# AC.net
KiCad netlist of a schematic drawn in Altium Designer
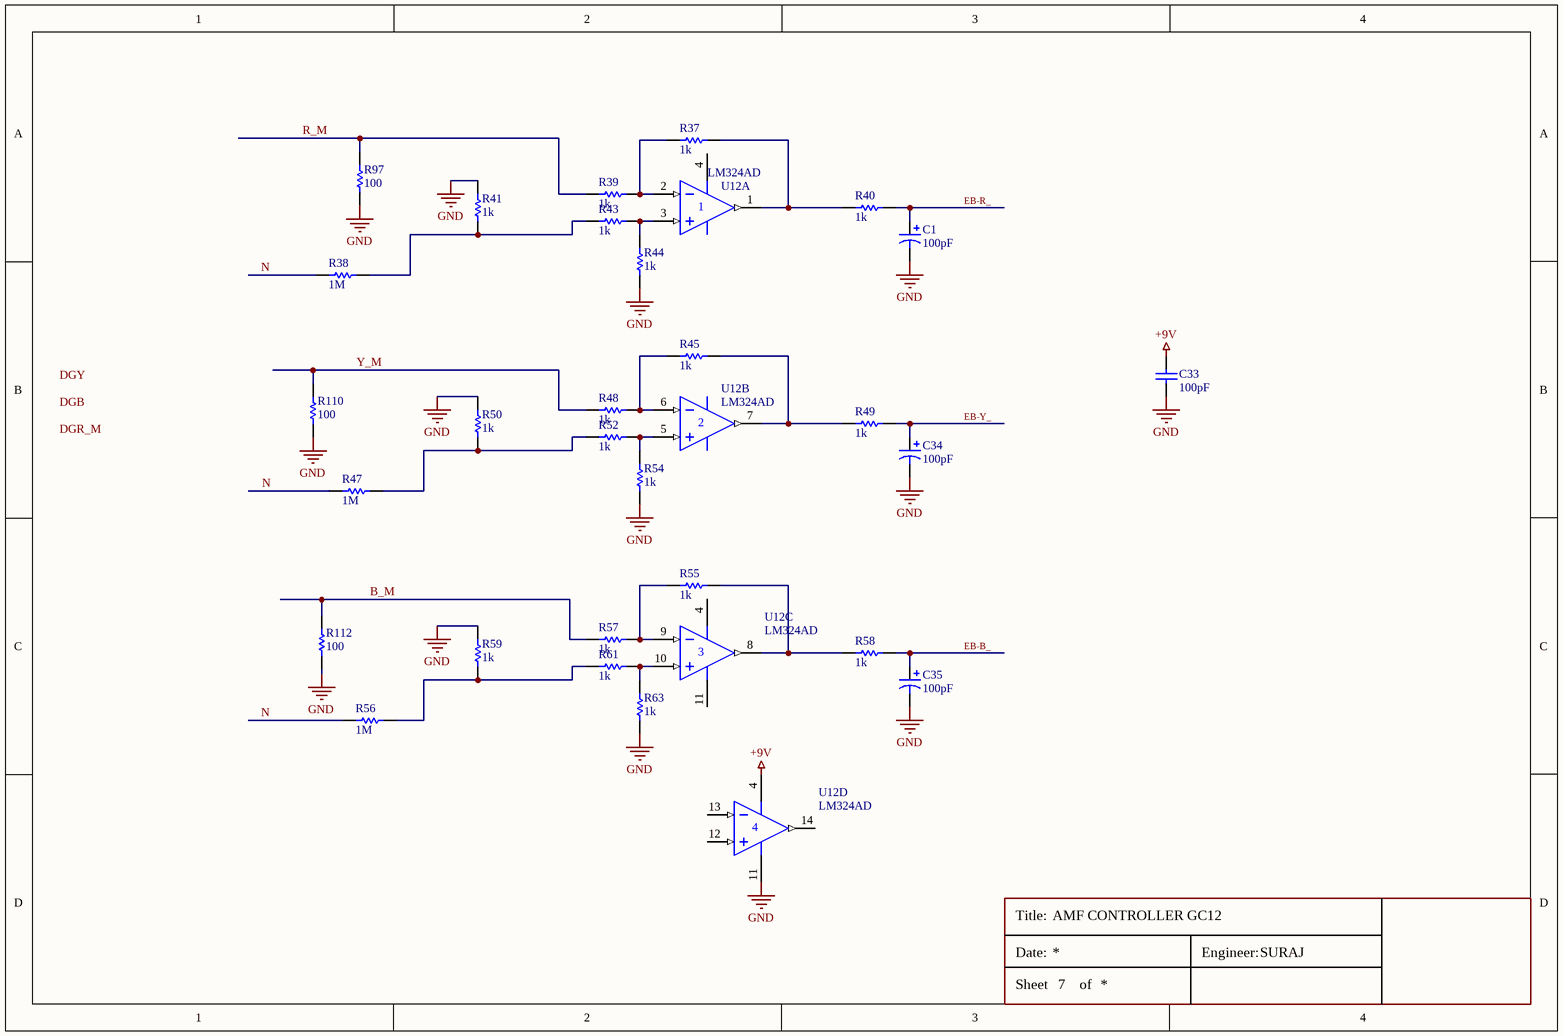
[diagram p0: AC.SchDoc]

(export (version "E")
  (design (tool "Eeschema 10.0.6"))
  (components
    (comp (ref "C1")
      (value "100pF")
      (footprint "Cap_.1")
      (description "Polarized Capacitor (Radial)")
      (fields (field (name "Comment") "10uF/63V") (field (name "PUBLISHER") "Altium Limited"))
      (libsource (lib "Miscellaneous Devices") (part "Cap Pol1"))
    )
    (comp (ref "C33")
      (value "100pF")
      (footprint "C1206VW")
      (description "Capacitor")
      (fields (field (name "Comment") ".1uF 1206") (field (name "PUBLISHER") "Altium Limited"))
      (libsource (lib "Miscellaneous Devices") (part "Cap"))
    )
    (comp (ref "C34")
      (value "100pF")
      (footprint "Cap_.1")
      (description "Polarized Capacitor (Radial)")
      (fields (field (name "Comment") "10uF/63V") (field (name "PUBLISHER") "Altium Limited"))
      (libsource (lib "Miscellaneous Devices") (part "Cap Pol1"))
    )
    (comp (ref "C35")
      (value "100pF")
      (footprint "Cap_.1")
      (description "Polarized Capacitor (Radial)")
      (fields (field (name "Comment") "10uF/63V") (field (name "PUBLISHER") "Altium Limited"))
      (libsource (lib "Miscellaneous Devices") (part "Cap Pol1"))
    )
    (comp (ref "R37")
      (value "1k")
      (footprint "R1206VW")
      (description "Semiconductor Resistor")
      (fields (field (name "Comment") "1M 1206") (field (name "PUBLISHER") "Altium Limited"))
      (libsource (lib "Miscellaneous Devices") (part "Res Semi"))
    )
    (comp (ref "R38")
      (value "1M")
      (footprint "RES_RAD_1W")
      (description "Semiconductor Resistor")
      (fields (field (name "Comment") "1M MFR") (field (name "PUBLISHER") "Altium Limited"))
      (libsource (lib "Miscellaneous Devices") (part "Res Semi"))
    )
    (comp (ref "R39")
      (value "1k")
      (footprint "R1206VW")
      (description "Semiconductor Resistor")
      (fields (field (name "Comment") "220K 1206") (field (name "PUBLISHER") "Altium Limited"))
      (libsource (lib "Miscellaneous Devices") (part "Res Semi"))
    )
    (comp (ref "R40")
      (value "1k")
      (footprint "R1206VW")
      (description "Semiconductor Resistor")
      (fields (field (name "Comment") "33K 1206") (field (name "PUBLISHER") "Altium Limited"))
      (libsource (lib "Miscellaneous Devices") (part "Res Semi"))
    )
    (comp (ref "R41")
      (value "1k")
      (footprint "R1206VW")
      (description "Semiconductor Resistor")
      (fields (field (name "Comment") "4.7K 1206") (field (name "PUBLISHER") "Altium Limited"))
      (libsource (lib "Miscellaneous Devices") (part "Res Semi"))
    )
    (comp (ref "R43")
      (value "1k")
      (footprint "R1206VW")
      (description "Semiconductor Resistor")
      (fields (field (name "Comment") "220K 1206") (field (name "PUBLISHER") "Altium Limited"))
      (libsource (lib "Miscellaneous Devices") (part "Res Semi"))
    )
    (comp (ref "R44")
      (value "1k")
      (footprint "R1206VW")
      (description "Semiconductor Resistor")
      (fields (field (name "Comment") "1M 1206") (field (name "PUBLISHER") "Altium Limited"))
      (libsource (lib "Miscellaneous Devices") (part "Res Semi"))
    )
    (comp (ref "R45")
      (value "1k")
      (footprint "R1206VW")
      (description "Semiconductor Resistor")
      (fields (field (name "Comment") "1M 1206") (field (name "PUBLISHER") "Altium Limited"))
      (libsource (lib "Miscellaneous Devices") (part "Res Semi"))
    )
    (comp (ref "R47")
      (value "1M")
      (footprint "RES_RAD_1W")
      (description "Semiconductor Resistor")
      (fields (field (name "Comment") "1M MFR") (field (name "PUBLISHER") "Altium Limited"))
      (libsource (lib "Miscellaneous Devices") (part "Res Semi"))
    )
    (comp (ref "R48")
      (value "1k")
      (footprint "R1206VW")
      (description "Semiconductor Resistor")
      (fields (field (name "Comment") "220K 1206") (field (name "PUBLISHER") "Altium Limited"))
      (libsource (lib "Miscellaneous Devices") (part "Res Semi"))
    )
    (comp (ref "R49")
      (value "1k")
      (footprint "R1206VW")
      (description "Semiconductor Resistor")
      (fields (field (name "Comment") "33K 1206") (field (name "PUBLISHER") "Altium Limited"))
      (libsource (lib "Miscellaneous Devices") (part "Res Semi"))
    )
    (comp (ref "R50")
      (value "1k")
      (footprint "R1206VW")
      (description "Semiconductor Resistor")
      (fields (field (name "Comment") "4.7K 1206") (field (name "PUBLISHER") "Altium Limited"))
      (libsource (lib "Miscellaneous Devices") (part "Res Semi"))
    )
    (comp (ref "R52")
      (value "1k")
      (footprint "R1206VW")
      (description "Semiconductor Resistor")
      (fields (field (name "Comment") "220K 1206") (field (name "PUBLISHER") "Altium Limited"))
      (libsource (lib "Miscellaneous Devices") (part "Res Semi"))
    )
    (comp (ref "R54")
      (value "1k")
      (footprint "R1206VW")
      (description "Semiconductor Resistor")
      (fields (field (name "Comment") "1M 1206") (field (name "PUBLISHER") "Altium Limited"))
      (libsource (lib "Miscellaneous Devices") (part "Res Semi"))
    )
    (comp (ref "R55")
      (value "1k")
      (footprint "R1206VW")
      (description "Semiconductor Resistor")
      (fields (field (name "Comment") "1M 1206") (field (name "PUBLISHER") "Altium Limited"))
      (libsource (lib "Miscellaneous Devices") (part "Res Semi"))
    )
    (comp (ref "R56")
      (value "1M")
      (footprint "RES_RAD_1W")
      (description "Semiconductor Resistor")
      (fields (field (name "Comment") "1M MFR") (field (name "PUBLISHER") "Altium Limited"))
      (libsource (lib "Miscellaneous Devices") (part "Res Semi"))
    )
    (comp (ref "R57")
      (value "1k")
      (footprint "R1206VW")
      (description "Semiconductor Resistor")
      (fields (field (name "Comment") "220K 1206") (field (name "PUBLISHER") "Altium Limited"))
      (libsource (lib "Miscellaneous Devices") (part "Res Semi"))
    )
    (comp (ref "R58")
      (value "1k")
      (footprint "R1206VW")
      (description "Semiconductor Resistor")
      (fields (field (name "Comment") "33K 1206") (field (name "PUBLISHER") "Altium Limited"))
      (libsource (lib "Miscellaneous Devices") (part "Res Semi"))
    )
    (comp (ref "R59")
      (value "1k")
      (footprint "R1206VW")
      (description "Semiconductor Resistor")
      (fields (field (name "Comment") "4.7K 1206") (field (name "PUBLISHER") "Altium Limited"))
      (libsource (lib "Miscellaneous Devices") (part "Res Semi"))
    )
    (comp (ref "R61")
      (value "1k")
      (footprint "R1206VW")
      (description "Semiconductor Resistor")
      (fields (field (name "Comment") "220K 1206") (field (name "PUBLISHER") "Altium Limited"))
      (libsource (lib "Miscellaneous Devices") (part "Res Semi"))
    )
    (comp (ref "R63")
      (value "1k")
      (footprint "R1206VW")
      (description "Semiconductor Resistor")
      (fields (field (name "Comment") "1M 1206") (field (name "PUBLISHER") "Altium Limited"))
      (libsource (lib "Miscellaneous Devices") (part "Res Semi"))
    )
    (comp (ref "R97")
      (value "100")
      (footprint "R1206VW")
      (description "Semiconductor Resistor")
      (fields (field (name "Comment") "4.7K 1206") (field (name "PUBLISHER") "Altium Limited"))
      (libsource (lib "Miscellaneous Devices") (part "Res Semi"))
    )
    (comp (ref "R110")
      (value "100")
      (footprint "R1206VW")
      (description "Semiconductor Resistor")
      (fields (field (name "Comment") "4.7K 1206") (field (name "PUBLISHER") "Altium Limited"))
      (libsource (lib "Miscellaneous Devices") (part "Res Semi"))
    )
    (comp (ref "R112")
      (value "100")
      (footprint "R1206VW")
      (description "Semiconductor Resistor")
      (fields (field (name "Comment") "4.7K 1206") (field (name "PUBLISHER") "Altium Limited"))
      (libsource (lib "Miscellaneous Devices") (part "Res Semi"))
    )
    (comp (ref "U12")
      (value "LM324AD")
      (footprint "D014_M")
      (description "Quadruple Operational Amplifier")
      (fields (field (name "PUBLISHER") "Altium Limited"))
      (libsource (lib "TI Operational Amplifier") (part "LM324AD"))
    )
  )
  (nets
    (net (code "1") (name "+9V") (class "Default")
      (node (ref "C33") (pin "2") (pinfunction "2_2") (pintype "passive"))
      (node (ref "U12") (pin "4") (pinfunction "V+_4") (pintype "power_in"))
    )
    (net (code "2") (name "/B_M") (class "Default")
      (node (ref "R112") (pin "2") (pinfunction "2_2") (pintype "passive"))
      (node (ref "R57") (pin "2") (pinfunction "2_2") (pintype "passive"))
    )
    (net (code "6") (name "/EB-B_") (class "Default")
      (node (ref "C35") (pin "1") (pinfunction "1_1") (pintype "passive"))
      (node (ref "R58") (pin "1") (pinfunction "1_1") (pintype "passive"))
    )
    (net (code "7") (name "/EB-R_") (class "Default")
      (node (ref "C1") (pin "1") (pinfunction "1_1") (pintype "passive"))
      (node (ref "R40") (pin "1") (pinfunction "1_1") (pintype "passive"))
    )
    (net (code "8") (name "/EB-Y_") (class "Default")
      (node (ref "C34") (pin "1") (pinfunction "1_1") (pintype "passive"))
      (node (ref "R49") (pin "1") (pinfunction "1_1") (pintype "passive"))
    )
    (net (code "9") (name "/N") (class "Default")
      (node (ref "R38") (pin "1") (pinfunction "1_1") (pintype "passive"))
      (node (ref "R47") (pin "1") (pinfunction "1_1") (pintype "passive"))
      (node (ref "R56") (pin "1") (pinfunction "1_1") (pintype "passive"))
    )
    (net (code "10") (name "/R_M") (class "Default")
      (node (ref "R39") (pin "2") (pinfunction "2_2") (pintype "passive"))
      (node (ref "R97") (pin "2") (pinfunction "2_2") (pintype "passive"))
    )
    (net (code "11") (name "/Y_M") (class "Default")
      (node (ref "R110") (pin "2") (pinfunction "2_2") (pintype "passive"))
      (node (ref "R48") (pin "2") (pinfunction "2_2") (pintype "passive"))
    )
    (net (code "12") (name "GND") (class "Default")
      (node (ref "C1") (pin "2") (pinfunction "2_2") (pintype "passive"))
      (node (ref "C33") (pin "1") (pinfunction "1_1") (pintype "passive"))
      (node (ref "C34") (pin "2") (pinfunction "2_2") (pintype "passive"))
      (node (ref "C35") (pin "2") (pinfunction "2_2") (pintype "passive"))
      (node (ref "R110") (pin "1") (pinfunction "1_1") (pintype "passive"))
      (node (ref "R112") (pin "1") (pinfunction "1_1") (pintype "passive"))
      (node (ref "R41") (pin "2") (pinfunction "2_2") (pintype "passive"))
      (node (ref "R44") (pin "1") (pinfunction "1_1") (pintype "passive"))
      (node (ref "R50") (pin "2") (pinfunction "2_2") (pintype "passive"))
      (node (ref "R54") (pin "1") (pinfunction "1_1") (pintype "passive"))
      (node (ref "R59") (pin "2") (pinfunction "2_2") (pintype "passive"))
      (node (ref "R63") (pin "1") (pinfunction "1_1") (pintype "passive"))
      (node (ref "R97") (pin "1") (pinfunction "1_1") (pintype "passive"))
      (node (ref "U12") (pin "11") (pinfunction "V-_11") (pintype "power_in"))
    )
    (net (code "13") (name "Net-(R38-Pad2)") (class "Default")
      (node (ref "R38") (pin "2") (pinfunction "2_2") (pintype "passive"))
      (node (ref "R41") (pin "1") (pinfunction "1_1") (pintype "passive"))
      (node (ref "R43") (pin "2") (pinfunction "2_2") (pintype "passive"))
    )
    (net (code "14") (name "Net-(R47-Pad2)") (class "Default")
      (node (ref "R47") (pin "2") (pinfunction "2_2") (pintype "passive"))
      (node (ref "R50") (pin "1") (pinfunction "1_1") (pintype "passive"))
      (node (ref "R52") (pin "2") (pinfunction "2_2") (pintype "passive"))
    )
    (net (code "15") (name "Net-(R56-Pad2)") (class "Default")
      (node (ref "R56") (pin "2") (pinfunction "2_2") (pintype "passive"))
      (node (ref "R59") (pin "1") (pinfunction "1_1") (pintype "passive"))
      (node (ref "R61") (pin "2") (pinfunction "2_2") (pintype "passive"))
    )
    (net (code "16") (name "Net-(U12A-IN+)") (class "Default")
      (node (ref "R43") (pin "1") (pinfunction "1_1") (pintype "passive"))
      (node (ref "R44") (pin "2") (pinfunction "2_2") (pintype "passive"))
      (node (ref "U12") (pin "3") (pinfunction "IN+_3") (pintype "input"))
    )
    (net (code "17") (name "Net-(U12A-IN-)") (class "Default")
      (node (ref "R37") (pin "2") (pinfunction "2_2") (pintype "passive"))
      (node (ref "R39") (pin "1") (pinfunction "1_1") (pintype "passive"))
      (node (ref "U12") (pin "2") (pinfunction "IN-_2") (pintype "input"))
    )
    (net (code "18") (name "Net-(U12A-OUT)") (class "Default")
      (node (ref "R37") (pin "1") (pinfunction "1_1") (pintype "passive"))
      (node (ref "R40") (pin "2") (pinfunction "2_2") (pintype "passive"))
      (node (ref "U12") (pin "1") (pinfunction "OUT_1") (pintype "output"))
    )
    (net (code "19") (name "Net-(U12B-IN+)") (class "Default")
      (node (ref "R52") (pin "1") (pinfunction "1_1") (pintype "passive"))
      (node (ref "R54") (pin "2") (pinfunction "2_2") (pintype "passive"))
      (node (ref "U12") (pin "5") (pinfunction "IN+_5") (pintype "input"))
    )
    (net (code "20") (name "Net-(U12B-IN-)") (class "Default")
      (node (ref "R45") (pin "2") (pinfunction "2_2") (pintype "passive"))
      (node (ref "R48") (pin "1") (pinfunction "1_1") (pintype "passive"))
      (node (ref "U12") (pin "6") (pinfunction "IN-_6") (pintype "input"))
    )
    (net (code "21") (name "Net-(U12B-OUT)") (class "Default")
      (node (ref "R45") (pin "1") (pinfunction "1_1") (pintype "passive"))
      (node (ref "R49") (pin "2") (pinfunction "2_2") (pintype "passive"))
      (node (ref "U12") (pin "7") (pinfunction "OUT_7") (pintype "output"))
    )
    (net (code "22") (name "Net-(U12C-IN+)") (class "Default")
      (node (ref "R61") (pin "1") (pinfunction "1_1") (pintype "passive"))
      (node (ref "R63") (pin "2") (pinfunction "2_2") (pintype "passive"))
      (node (ref "U12") (pin "10") (pinfunction "IN+_10") (pintype "input"))
    )
    (net (code "23") (name "Net-(U12C-IN-)") (class "Default")
      (node (ref "R55") (pin "2") (pinfunction "2_2") (pintype "passive"))
      (node (ref "R57") (pin "1") (pinfunction "1_1") (pintype "passive"))
      (node (ref "U12") (pin "9") (pinfunction "IN-_9") (pintype "input"))
    )
    (net (code "24") (name "Net-(U12C-OUT)") (class "Default")
      (node (ref "R55") (pin "1") (pinfunction "1_1") (pintype "passive"))
      (node (ref "R58") (pin "2") (pinfunction "2_2") (pintype "passive"))
      (node (ref "U12") (pin "8") (pinfunction "OUT_8") (pintype "output"))
    )
    (net (code "25") (name "unconnected-(U12D-IN+-Pad12)") (class "Default")
      (node (ref "U12") (pin "12") (pinfunction "IN+_12") (pintype "input"))
    )
    (net (code "26") (name "unconnected-(U12D-IN--Pad13)") (class "Default")
      (node (ref "U12") (pin "13") (pinfunction "IN-_13") (pintype "input"))
    )
    (net (code "27") (name "unconnected-(U12D-OUT-Pad14)") (class "Default")
      (node (ref "U12") (pin "14") (pinfunction "OUT_14") (pintype "output"))
    )
  )
)
